# cj-mini.net
KiCad netlist of a schematic drawn in EAGLE
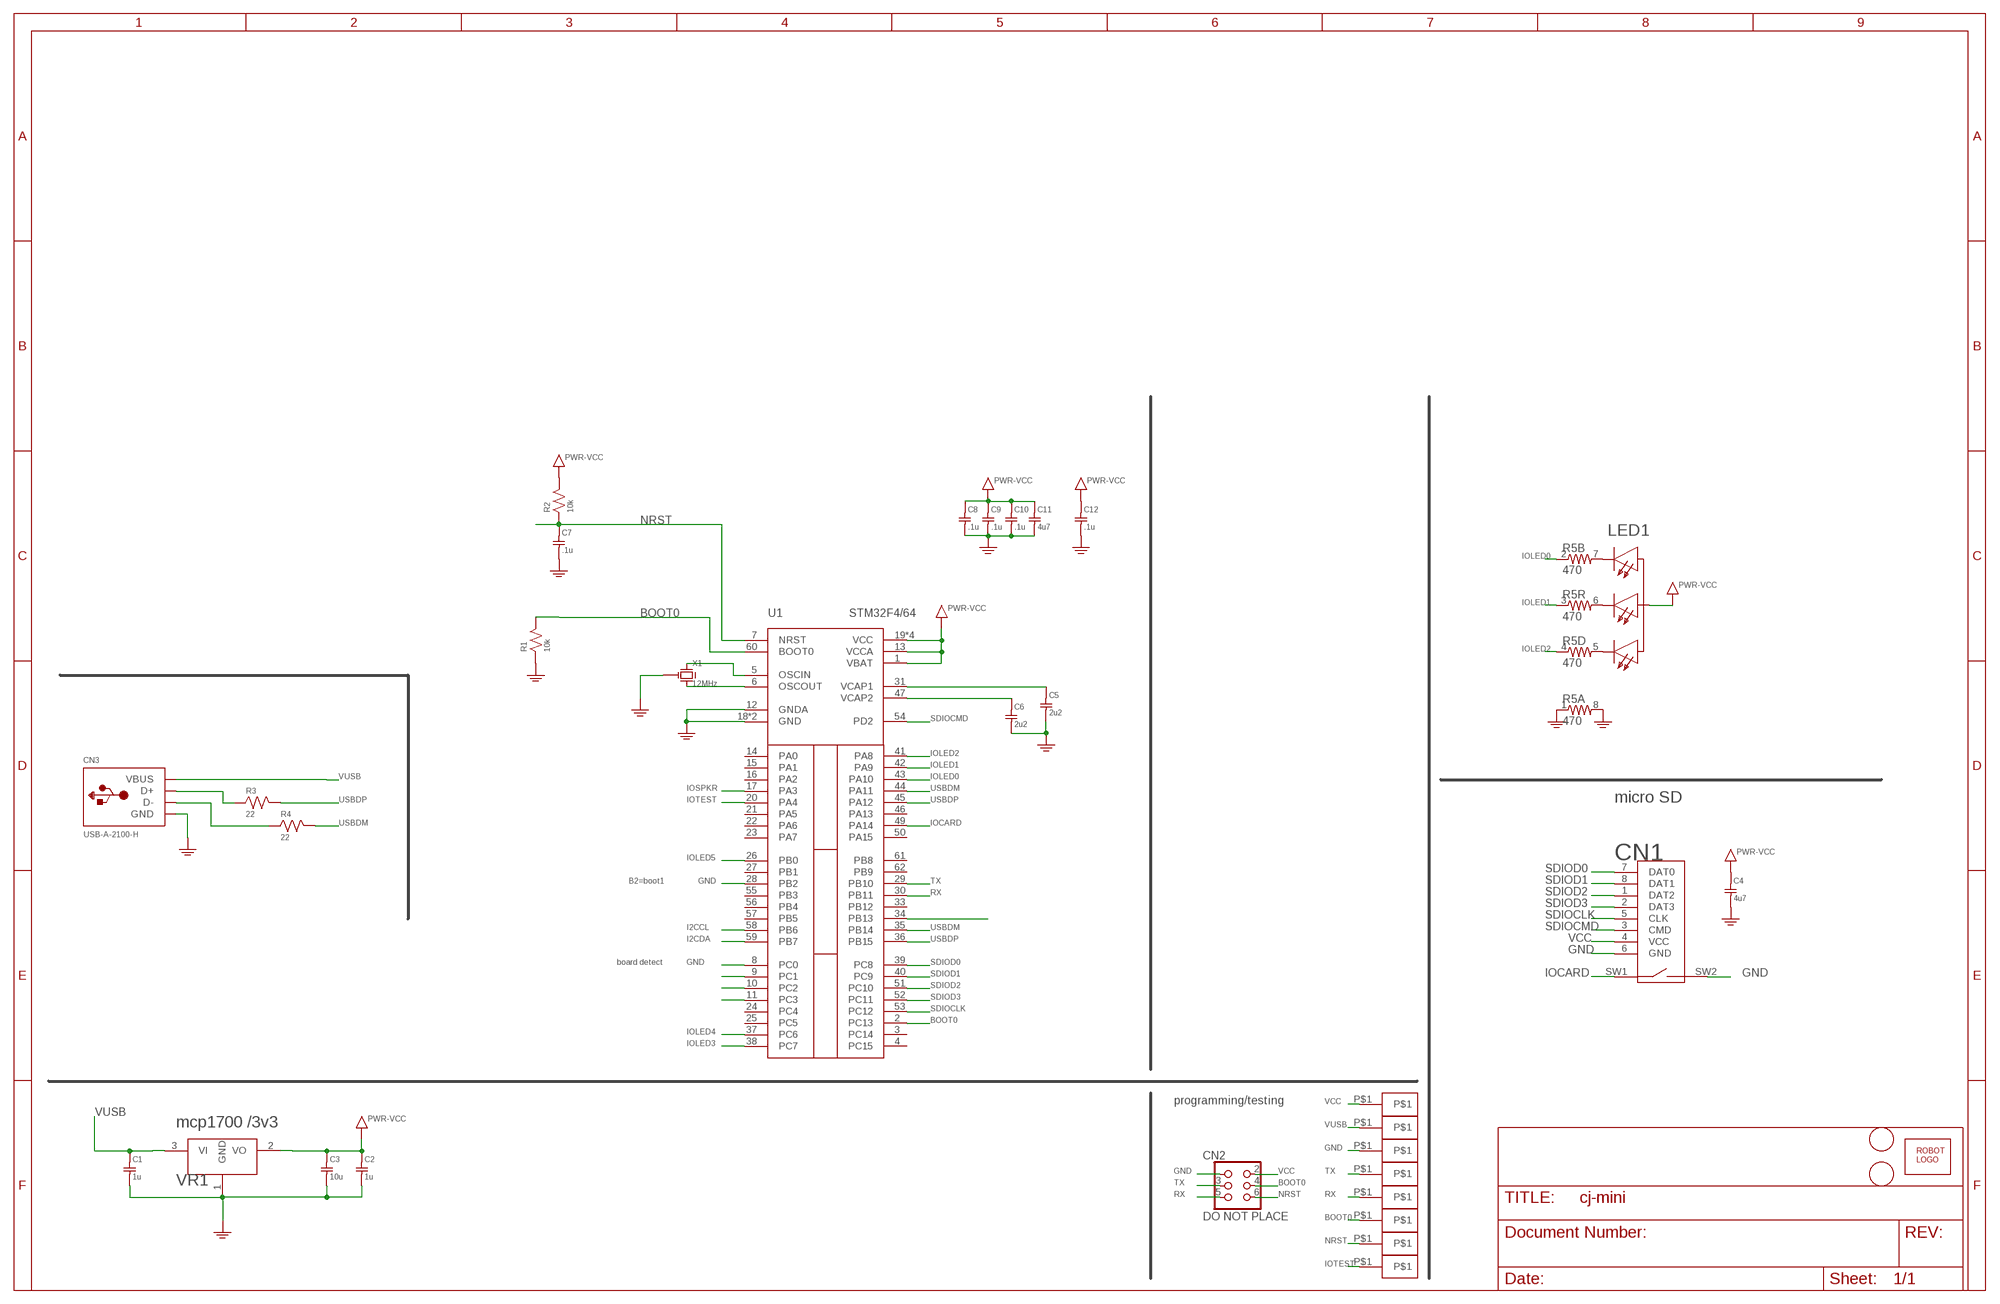
[diagram p0: schematic, sheet 1]

(export (version "E")
  (design (tool "Eeschema 10.0.6"))
  (components
    (comp (ref "C1")
      (value "1u")
      (footprint "eagle-import:SMD0603")
      (libsource (lib "eagle-import") (part "C0603"))
    )
    (comp (ref "C2")
      (value "1u")
      (footprint "eagle-import:SMD0603")
      (libsource (lib "eagle-import") (part "C0603"))
    )
    (comp (ref "C3")
      (value "10u")
      (footprint "eagle-import:SMD0603")
      (libsource (lib "eagle-import") (part "C0603"))
    )
    (comp (ref "C4")
      (value "4u7")
      (footprint "eagle-import:SMD0603")
      (libsource (lib "eagle-import") (part "C0603"))
    )
    (comp (ref "C5")
      (value "2u2")
      (footprint "eagle-import:SMD0603")
      (libsource (lib "eagle-import") (part "C0603"))
    )
    (comp (ref "C6")
      (value "2u2")
      (footprint "eagle-import:SMD0603")
      (libsource (lib "eagle-import") (part "C0603"))
    )
    (comp (ref "C7")
      (value ".1u")
      (footprint "eagle-import:SMD0603")
      (libsource (lib "eagle-import") (part "C0603"))
    )
    (comp (ref "C8")
      (value ".1u")
      (footprint "eagle-import:SMD0603")
      (libsource (lib "eagle-import") (part "C0603"))
    )
    (comp (ref "C9")
      (value ".1u")
      (footprint "eagle-import:SMD0603")
      (libsource (lib "eagle-import") (part "C0603"))
    )
    (comp (ref "C10")
      (value ".1u")
      (footprint "eagle-import:SMD0603")
      (libsource (lib "eagle-import") (part "C0603"))
    )
    (comp (ref "C11")
      (value "4u7")
      (footprint "eagle-import:SMD0603")
      (libsource (lib "eagle-import") (part "C0603"))
    )
    (comp (ref "C12")
      (value ".1u")
      (footprint "eagle-import:SMD0603")
      (libsource (lib "eagle-import") (part "C0603"))
    )
    (comp (ref "CN1")
      (value "MICROSDPLAIN")
      (footprint "eagle-import:MICROSD_MOLEX_FRONT_PLAIN")
      (libsource (lib "eagle-import") (part "MICROSDPLAIN"))
    )
    (comp (ref "CN2")
      (value "DO NOT PLACE")
      (footprint "eagle-import:HEADER-3X2-PTH1.27")
      (libsource (lib "eagle-import") (part "HEADER-3X2-PTH1.27"))
    )
    (comp (ref "CN3")
      (value "USB-A-2100-H")
      (footprint "eagle-import:MOLEX_480372100-HOLE")
      (libsource (lib "eagle-import") (part "USB-A-2100-H"))
    )
    (comp (ref "CN4")
      (value "HEADER-1X1-SPOT")
      (footprint "eagle-import:SPOT")
      (libsource (lib "eagle-import") (part "HEADER-1X1-SPOT"))
    )
    (comp (ref "CN5")
      (value "HEADER-1X1-SPOT")
      (footprint "eagle-import:SPOT")
      (libsource (lib "eagle-import") (part "HEADER-1X1-SPOT"))
    )
    (comp (ref "CN6")
      (value "HEADER-1X1-SPOT")
      (footprint "eagle-import:SPOT")
      (libsource (lib "eagle-import") (part "HEADER-1X1-SPOT"))
    )
    (comp (ref "CN7")
      (value "HEADER-1X1-SPOT")
      (footprint "eagle-import:SPOT")
      (libsource (lib "eagle-import") (part "HEADER-1X1-SPOT"))
    )
    (comp (ref "CN8")
      (value "HEADER-1X1-SPOT")
      (footprint "eagle-import:SPOT")
      (libsource (lib "eagle-import") (part "HEADER-1X1-SPOT"))
    )
    (comp (ref "CN9")
      (value "HEADER-1X1-SPOT")
      (footprint "eagle-import:SPOT")
      (libsource (lib "eagle-import") (part "HEADER-1X1-SPOT"))
    )
    (comp (ref "CN10")
      (value "HEADER-1X1-SPOT")
      (footprint "eagle-import:SPOT")
      (libsource (lib "eagle-import") (part "HEADER-1X1-SPOT"))
    )
    (comp (ref "CN11")
      (value "HEADER-1X1-SPOT")
      (footprint "eagle-import:SPOT")
      (libsource (lib "eagle-import") (part "HEADER-1X1-SPOT"))
    )
    (comp (ref "LED1")
      (value "LED-RGB-CA-PLCC4")
      (footprint "eagle-import:PLCC4-3228")
      (libsource (lib "eagle-import") (part "LED-RGB-CA-PLCC4"))
    )
    (comp (ref "R1")
      (value "10k")
      (footprint "eagle-import:SMD0603")
      (libsource (lib "eagle-import") (part "R0603"))
    )
    (comp (ref "R2")
      (value "10k")
      (footprint "eagle-import:SMD0603")
      (libsource (lib "eagle-import") (part "R0603"))
    )
    (comp (ref "R3")
      (value "22")
      (footprint "eagle-import:SMD0603")
      (libsource (lib "eagle-import") (part "R0603"))
    )
    (comp (ref "R4")
      (value "22")
      (footprint "eagle-import:SMD0603")
      (libsource (lib "eagle-import") (part "R0603"))
    )
    (comp (ref "R5")
      (value "470")
      (footprint "eagle-import:SMD-0603-ARV")
      (libsource (lib "eagle-import") (part "R-ARRAY40603-ARV"))
    )
    (comp (ref "U$1")
      (value "ROBOTMAN-LOGO")
      (footprint "eagle-import:ROBOTMAN-LOGO")
      (libsource (lib "eagle-import") (part "ROBOTMAN-LOGO"))
    )
    (comp (ref "U$2")
      (value "FIDUCIAL")
      (footprint "eagle-import:FIDUCIAL_1MM")
      (libsource (lib "eagle-import") (part "FIDUCIAL"))
    )
    (comp (ref "U$3")
      (value "FIDUCIAL")
      (footprint "eagle-import:FIDUCIAL_1MM")
      (libsource (lib "eagle-import") (part "FIDUCIAL"))
    )
    (comp (ref "U1")
      (value "STM32F4/64")
      (footprint "eagle-import:TQFP64")
      (libsource (lib "eagle-import") (part "STM32F4/64"))
    )
    (comp (ref "VR1")
      (value "mcp1700 /3v3")
      (footprint "eagle-import:SOT-23-3@1")
      (libsource (lib "eagle-import") (part "REGULATOR-SOT23-3"))
    )
    (comp (ref "X1")
      (value "12MHz")
      (footprint "eagle-import:RESONATOR-CSTCE")
      (libsource (lib "eagle-import") (part "RESONATORCTCE"))
    )
  )
  (nets
    (net (code "1") (name "/BOOT0") (class "Default")
      (node (ref "CN2") (pin "4") (pinfunction "P$4_4") (pintype "passive"))
      (node (ref "CN8") (pin "P$1") (pinfunction "P$1_P$1") (pintype "bidirectional"))
      (node (ref "R1") (pin "2") (pinfunction "P$2_2") (pintype "passive"))
      (node (ref "U1") (pin "2") (pinfunction "PC13_2") (pintype "bidirectional"))
      (node (ref "U1") (pin "60") (pinfunction "BOOT0_60") (pintype "bidirectional"))
    )
    (net (code "2") (name "/I2CCL") (class "Default")
      (node (ref "U1") (pin "58") (pinfunction "PB6_58") (pintype "bidirectional"))
    )
    (net (code "3") (name "/I2CDA") (class "Default")
      (node (ref "U1") (pin "59") (pinfunction "PB7_59") (pintype "bidirectional"))
    )
    (net (code "4") (name "/IOCARD") (class "Default")
      (node (ref "CN1") (pin "SW1") (pinfunction "SW1_SW1") (pintype "bidirectional"))
      (node (ref "U1") (pin "49") (pinfunction "PA14_49") (pintype "bidirectional"))
    )
    (net (code "5") (name "/IOLED0") (class "Default")
      (node (ref "R5") (pin "2") (pinfunction "1_2") (pintype "passive"))
      (node (ref "U1") (pin "43") (pinfunction "PA10_43") (pintype "bidirectional"))
    )
    (net (code "6") (name "/IOLED1") (class "Default")
      (node (ref "R5") (pin "3") (pinfunction "1_3") (pintype "passive"))
      (node (ref "U1") (pin "42") (pinfunction "PA9_42") (pintype "bidirectional"))
    )
    (net (code "7") (name "/IOLED2") (class "Default")
      (node (ref "R5") (pin "4") (pinfunction "1_4") (pintype "passive"))
      (node (ref "U1") (pin "41") (pinfunction "PA8_41") (pintype "bidirectional"))
    )
    (net (code "8") (name "/IOLED3") (class "Default")
      (node (ref "U1") (pin "38") (pinfunction "PC7_38") (pintype "bidirectional"))
    )
    (net (code "9") (name "/IOLED4") (class "Default")
      (node (ref "U1") (pin "37") (pinfunction "PC6_37") (pintype "bidirectional"))
    )
    (net (code "10") (name "/IOLED5") (class "Default")
      (node (ref "U1") (pin "26") (pinfunction "PB0_26") (pintype "bidirectional"))
    )
    (net (code "11") (name "/IOSPKR") (class "Default")
      (node (ref "U1") (pin "17") (pinfunction "PA3_17") (pintype "bidirectional"))
    )
    (net (code "12") (name "/IOTEST") (class "Default")
      (node (ref "CN11") (pin "P$1") (pinfunction "P$1_P$1") (pintype "bidirectional"))
      (node (ref "U1") (pin "20") (pinfunction "PA4_20") (pintype "bidirectional"))
    )
    (net (code "13") (name "/NRST") (class "Default")
      (node (ref "C7") (pin "1") (pinfunction "P$1_1") (pintype "passive"))
      (node (ref "CN2") (pin "6") (pinfunction "P$6_6") (pintype "passive"))
      (node (ref "CN9") (pin "P$1") (pinfunction "P$1_P$1") (pintype "bidirectional"))
      (node (ref "R2") (pin "1") (pinfunction "P$1_1") (pintype "passive"))
      (node (ref "U1") (pin "7") (pinfunction "NRST_7") (pintype "bidirectional"))
    )
    (net (code "14") (name "/RX") (class "Default")
      (node (ref "CN2") (pin "5") (pinfunction "P$5_5") (pintype "passive"))
      (node (ref "CN7") (pin "P$1") (pinfunction "P$1_P$1") (pintype "bidirectional"))
      (node (ref "U1") (pin "30") (pinfunction "PB11_30") (pintype "bidirectional"))
    )
    (net (code "15") (name "/SDIOCLK") (class "Default")
      (node (ref "CN1") (pin "5") (pinfunction "CLK_5") (pintype "bidirectional"))
      (node (ref "U1") (pin "53") (pinfunction "PC12_53") (pintype "bidirectional"))
    )
    (net (code "16") (name "/SDIOCMD") (class "Default")
      (node (ref "CN1") (pin "3") (pinfunction "CMD_3") (pintype "bidirectional"))
      (node (ref "U1") (pin "54") (pinfunction "PD2_54") (pintype "bidirectional"))
    )
    (net (code "17") (name "/SDIOD0") (class "Default")
      (node (ref "CN1") (pin "7") (pinfunction "DAT0_7") (pintype "bidirectional"))
      (node (ref "U1") (pin "39") (pinfunction "PC8_39") (pintype "bidirectional"))
    )
    (net (code "18") (name "/SDIOD1") (class "Default")
      (node (ref "CN1") (pin "8") (pinfunction "DAT1_8") (pintype "bidirectional"))
      (node (ref "U1") (pin "40") (pinfunction "PC9_40") (pintype "bidirectional"))
    )
    (net (code "19") (name "/SDIOD2") (class "Default")
      (node (ref "CN1") (pin "1") (pinfunction "DAT2_1") (pintype "bidirectional"))
      (node (ref "U1") (pin "51") (pinfunction "PC10_51") (pintype "bidirectional"))
    )
    (net (code "20") (name "/SDIOD3") (class "Default")
      (node (ref "CN1") (pin "2") (pinfunction "DAT3_2") (pintype "bidirectional"))
      (node (ref "U1") (pin "52") (pinfunction "PC11_52") (pintype "bidirectional"))
    )
    (net (code "21") (name "/TX") (class "Default")
      (node (ref "CN2") (pin "3") (pinfunction "P$3_3") (pintype "passive"))
      (node (ref "CN6") (pin "P$1") (pinfunction "P$1_P$1") (pintype "bidirectional"))
      (node (ref "U1") (pin "29") (pinfunction "PB10_29") (pintype "bidirectional"))
    )
    (net (code "22") (name "/USBDM") (class "Default")
      (node (ref "R4") (pin "2") (pinfunction "P$2_2") (pintype "passive"))
      (node (ref "U1") (pin "35") (pinfunction "PB14_35") (pintype "bidirectional"))
      (node (ref "U1") (pin "44") (pinfunction "PA11_44") (pintype "bidirectional"))
    )
    (net (code "23") (name "/USBDP") (class "Default")
      (node (ref "R3") (pin "2") (pinfunction "P$2_2") (pintype "passive"))
      (node (ref "U1") (pin "36") (pinfunction "PB15_36") (pintype "bidirectional"))
      (node (ref "U1") (pin "45") (pinfunction "PA12_45") (pintype "bidirectional"))
    )
    (net (code "24") (name "/VUSB") (class "Default")
      (node (ref "C1") (pin "1") (pinfunction "P$1_1") (pintype "passive"))
      (node (ref "CN3") (pin "1") (pinfunction "VBUS_1") (pintype "power_in"))
      (node (ref "CN4") (pin "P$1") (pinfunction "P$1_P$1") (pintype "bidirectional"))
      (node (ref "VR1") (pin "3") (pinfunction "VI_3") (pintype "bidirectional"))
    )
    (net (code "25") (name "Net-(C5-P$1)") (class "Default")
      (node (ref "C5") (pin "1") (pinfunction "P$1_1") (pintype "passive"))
      (node (ref "U1") (pin "31") (pinfunction "VCAP1_31") (pintype "bidirectional"))
    )
    (net (code "26") (name "Net-(C6-P$1)") (class "Default")
      (node (ref "C6") (pin "1") (pinfunction "P$1_1") (pintype "passive"))
      (node (ref "U1") (pin "47") (pinfunction "VCAP2_47") (pintype "bidirectional"))
    )
    (net (code "27") (name "Net-(CN3-D+)") (class "Default")
      (node (ref "CN3") (pin "3") (pinfunction "D+_3") (pintype "bidirectional"))
      (node (ref "R3") (pin "1") (pinfunction "P$1_1") (pintype "passive"))
    )
    (net (code "28") (name "Net-(CN3-D-)") (class "Default")
      (node (ref "CN3") (pin "2") (pinfunction "D-_2") (pintype "bidirectional"))
      (node (ref "R4") (pin "1") (pinfunction "P$1_1") (pintype "passive"))
    )
    (net (code "29") (name "Net-(LED1-CB)") (class "Default")
      (node (ref "LED1") (pin "P$4") (pinfunction "CB_P$4") (pintype "passive"))
      (node (ref "R5") (pin "6") (pinfunction "2_6") (pintype "passive"))
    )
    (net (code "30") (name "Net-(LED1-CG)") (class "Default")
      (node (ref "LED1") (pin "P$3") (pinfunction "CG_P$3") (pintype "passive"))
      (node (ref "R5") (pin "7") (pinfunction "2_7") (pintype "passive"))
    )
    (net (code "31") (name "Net-(LED1-CR)") (class "Default")
      (node (ref "LED1") (pin "P$2") (pinfunction "CR_P$2") (pintype "passive"))
      (node (ref "R5") (pin "5") (pinfunction "2_5") (pintype "passive"))
    )
    (net (code "32") (name "Net-(U1-OSCIN)") (class "Default")
      (node (ref "U1") (pin "5") (pinfunction "OSCIN_5") (pintype "bidirectional"))
      (node (ref "X1") (pin "1") (pinfunction "X1_1") (pintype "passive"))
    )
    (net (code "33") (name "Net-(U1-OSCOUT)") (class "Default")
      (node (ref "U1") (pin "6") (pinfunction "OSCOUT_6") (pintype "bidirectional"))
      (node (ref "X1") (pin "3") (pinfunction "X2_3") (pintype "passive"))
    )
    (net (code "34") (name "PWR-GND") (class "Default")
      (node (ref "C1") (pin "2") (pinfunction "P$2_2") (pintype "passive"))
      (node (ref "C10") (pin "2") (pinfunction "P$2_2") (pintype "passive"))
      (node (ref "C11") (pin "2") (pinfunction "P$2_2") (pintype "passive"))
      (node (ref "C12") (pin "2") (pinfunction "P$2_2") (pintype "passive"))
      (node (ref "C2") (pin "2") (pinfunction "P$2_2") (pintype "passive"))
      (node (ref "C3") (pin "2") (pinfunction "P$2_2") (pintype "passive"))
      (node (ref "C4") (pin "2") (pinfunction "P$2_2") (pintype "passive"))
      (node (ref "C5") (pin "2") (pinfunction "P$2_2") (pintype "passive"))
      (node (ref "C6") (pin "2") (pinfunction "P$2_2") (pintype "passive"))
      (node (ref "C7") (pin "2") (pinfunction "P$2_2") (pintype "passive"))
      (node (ref "C8") (pin "2") (pinfunction "P$2_2") (pintype "passive"))
      (node (ref "C9") (pin "2") (pinfunction "P$2_2") (pintype "passive"))
      (node (ref "CN1") (pin "6") (pinfunction "GND_6") (pintype "bidirectional"))
      (node (ref "CN1") (pin "SW2") (pinfunction "SW2_SW2") (pintype "bidirectional"))
      (node (ref "CN2") (pin "1") (pinfunction "P$1_1") (pintype "passive"))
      (node (ref "CN3") (pin "4") (pinfunction "GND_4") (pintype "power_in"))
      (node (ref "CN3") (pin "P$1") (pinfunction "GND_P$1") (pintype "power_in"))
      (node (ref "CN3") (pin "P$2") (pinfunction "GND_P$2") (pintype "power_in"))
      (node (ref "CN5") (pin "P$1") (pinfunction "P$1_P$1") (pintype "bidirectional"))
      (node (ref "R1") (pin "1") (pinfunction "P$1_1") (pintype "passive"))
      (node (ref "R5") (pin "1") (pinfunction "1_1") (pintype "passive"))
      (node (ref "R5") (pin "8") (pinfunction "2_8") (pintype "passive"))
      (node (ref "U1") (pin "12") (pinfunction "GNDA_12") (pintype "bidirectional"))
      (node (ref "U1") (pin "18") (pinfunction "GND_18") (pintype "bidirectional"))
      (node (ref "U1") (pin "28") (pinfunction "PB2_28") (pintype "bidirectional"))
      (node (ref "U1") (pin "63") (pinfunction "GND_63") (pintype "bidirectional"))
      (node (ref "U1") (pin "8") (pinfunction "PC0_8") (pintype "bidirectional"))
      (node (ref "VR1") (pin "1") (pinfunction "GND_1") (pintype "bidirectional"))
      (node (ref "X1") (pin "2") (pinfunction "G_2") (pintype "input"))
    )
    (net (code "35") (name "PWR-VCC") (class "Default")
      (node (ref "C10") (pin "1") (pinfunction "P$1_1") (pintype "passive"))
      (node (ref "C11") (pin "1") (pinfunction "P$1_1") (pintype "passive"))
      (node (ref "C12") (pin "1") (pinfunction "P$1_1") (pintype "passive"))
      (node (ref "C2") (pin "1") (pinfunction "P$1_1") (pintype "passive"))
      (node (ref "C3") (pin "1") (pinfunction "P$1_1") (pintype "passive"))
      (node (ref "C4") (pin "1") (pinfunction "P$1_1") (pintype "passive"))
      (node (ref "C8") (pin "1") (pinfunction "P$1_1") (pintype "passive"))
      (node (ref "C9") (pin "1") (pinfunction "P$1_1") (pintype "passive"))
      (node (ref "CN1") (pin "4") (pinfunction "VCC_4") (pintype "bidirectional"))
      (node (ref "CN10") (pin "P$1") (pinfunction "P$1_P$1") (pintype "bidirectional"))
      (node (ref "CN2") (pin "2") (pinfunction "P$2_2") (pintype "passive"))
      (node (ref "LED1") (pin "P$1") (pinfunction "A_P$1") (pintype "passive"))
      (node (ref "R2") (pin "2") (pinfunction "P$2_2") (pintype "passive"))
      (node (ref "U1") (pin "1") (pinfunction "VBAT_1") (pintype "bidirectional"))
      (node (ref "U1") (pin "13") (pinfunction "VCCA_13") (pintype "bidirectional"))
      (node (ref "U1") (pin "19") (pinfunction "VCC_19") (pintype "bidirectional"))
      (node (ref "U1") (pin "32") (pinfunction "VCC_32") (pintype "bidirectional"))
      (node (ref "U1") (pin "48") (pinfunction "VCC_48") (pintype "bidirectional"))
      (node (ref "U1") (pin "64") (pinfunction "VCC_64") (pintype "bidirectional"))
      (node (ref "VR1") (pin "2") (pinfunction "VO_2") (pintype "bidirectional"))
    )
    (net (code "36") (name "unconnected-(U1-PA0-Pad14)") (class "Default")
      (node (ref "U1") (pin "14") (pinfunction "PA0_14") (pintype "bidirectional"))
    )
    (net (code "37") (name "unconnected-(U1-PA1-Pad15)") (class "Default")
      (node (ref "U1") (pin "15") (pinfunction "PA1_15") (pintype "bidirectional"))
    )
    (net (code "38") (name "unconnected-(U1-PA2-Pad16)") (class "Default")
      (node (ref "U1") (pin "16") (pinfunction "PA2_16") (pintype "bidirectional"))
    )
    (net (code "39") (name "unconnected-(U1-PA5-Pad21)") (class "Default")
      (node (ref "U1") (pin "21") (pinfunction "PA5_21") (pintype "bidirectional"))
    )
    (net (code "40") (name "unconnected-(U1-PA6-Pad22)") (class "Default")
      (node (ref "U1") (pin "22") (pinfunction "PA6_22") (pintype "bidirectional"))
    )
    (net (code "41") (name "unconnected-(U1-PA7-Pad23)") (class "Default")
      (node (ref "U1") (pin "23") (pinfunction "PA7_23") (pintype "bidirectional"))
    )
    (net (code "42") (name "unconnected-(U1-PA13-Pad46)") (class "Default")
      (node (ref "U1") (pin "46") (pinfunction "PA13_46") (pintype "bidirectional"))
    )
    (net (code "43") (name "unconnected-(U1-PA15-Pad50)") (class "Default")
      (node (ref "U1") (pin "50") (pinfunction "PA15_50") (pintype "bidirectional"))
    )
    (net (code "44") (name "unconnected-(U1-PB1-Pad27)") (class "Default")
      (node (ref "U1") (pin "27") (pinfunction "PB1_27") (pintype "bidirectional"))
    )
    (net (code "45") (name "unconnected-(U1-PB3-Pad55)") (class "Default")
      (node (ref "U1") (pin "55") (pinfunction "PB3_55") (pintype "bidirectional"))
    )
    (net (code "46") (name "unconnected-(U1-PB4-Pad56)") (class "Default")
      (node (ref "U1") (pin "56") (pinfunction "PB4_56") (pintype "bidirectional"))
    )
    (net (code "47") (name "unconnected-(U1-PB5-Pad57)") (class "Default")
      (node (ref "U1") (pin "57") (pinfunction "PB5_57") (pintype "bidirectional"))
    )
    (net (code "48") (name "unconnected-(U1-PB8-Pad61)") (class "Default")
      (node (ref "U1") (pin "61") (pinfunction "PB8_61") (pintype "bidirectional"))
    )
    (net (code "49") (name "unconnected-(U1-PB9-Pad62)") (class "Default")
      (node (ref "U1") (pin "62") (pinfunction "PB9_62") (pintype "bidirectional"))
    )
    (net (code "50") (name "unconnected-(U1-PB12-Pad33)") (class "Default")
      (node (ref "U1") (pin "33") (pinfunction "PB12_33") (pintype "bidirectional"))
    )
    (net (code "51") (name "unconnected-(U1-PB13-Pad34)") (class "Default")
      (node (ref "U1") (pin "34") (pinfunction "PB13_34") (pintype "bidirectional"))
    )
    (net (code "52") (name "unconnected-(U1-PC1-Pad9)") (class "Default")
      (node (ref "U1") (pin "9") (pinfunction "PC1_9") (pintype "bidirectional"))
    )
    (net (code "53") (name "unconnected-(U1-PC2-Pad10)") (class "Default")
      (node (ref "U1") (pin "10") (pinfunction "PC2_10") (pintype "bidirectional"))
    )
    (net (code "54") (name "unconnected-(U1-PC3-Pad11)") (class "Default")
      (node (ref "U1") (pin "11") (pinfunction "PC3_11") (pintype "bidirectional"))
    )
    (net (code "55") (name "unconnected-(U1-PC4-Pad24)") (class "Default")
      (node (ref "U1") (pin "24") (pinfunction "PC4_24") (pintype "bidirectional"))
    )
    (net (code "56") (name "unconnected-(U1-PC5-Pad25)") (class "Default")
      (node (ref "U1") (pin "25") (pinfunction "PC5_25") (pintype "bidirectional"))
    )
    (net (code "57") (name "unconnected-(U1-PC14-Pad3)") (class "Default")
      (node (ref "U1") (pin "3") (pinfunction "PC14_3") (pintype "bidirectional"))
    )
    (net (code "58") (name "unconnected-(U1-PC15-Pad4)") (class "Default")
      (node (ref "U1") (pin "4") (pinfunction "PC15_4") (pintype "bidirectional"))
    )
  )
)
